# Sch_ma_Global.net
KiCad netlist of a schematic drawn in Altium Designer
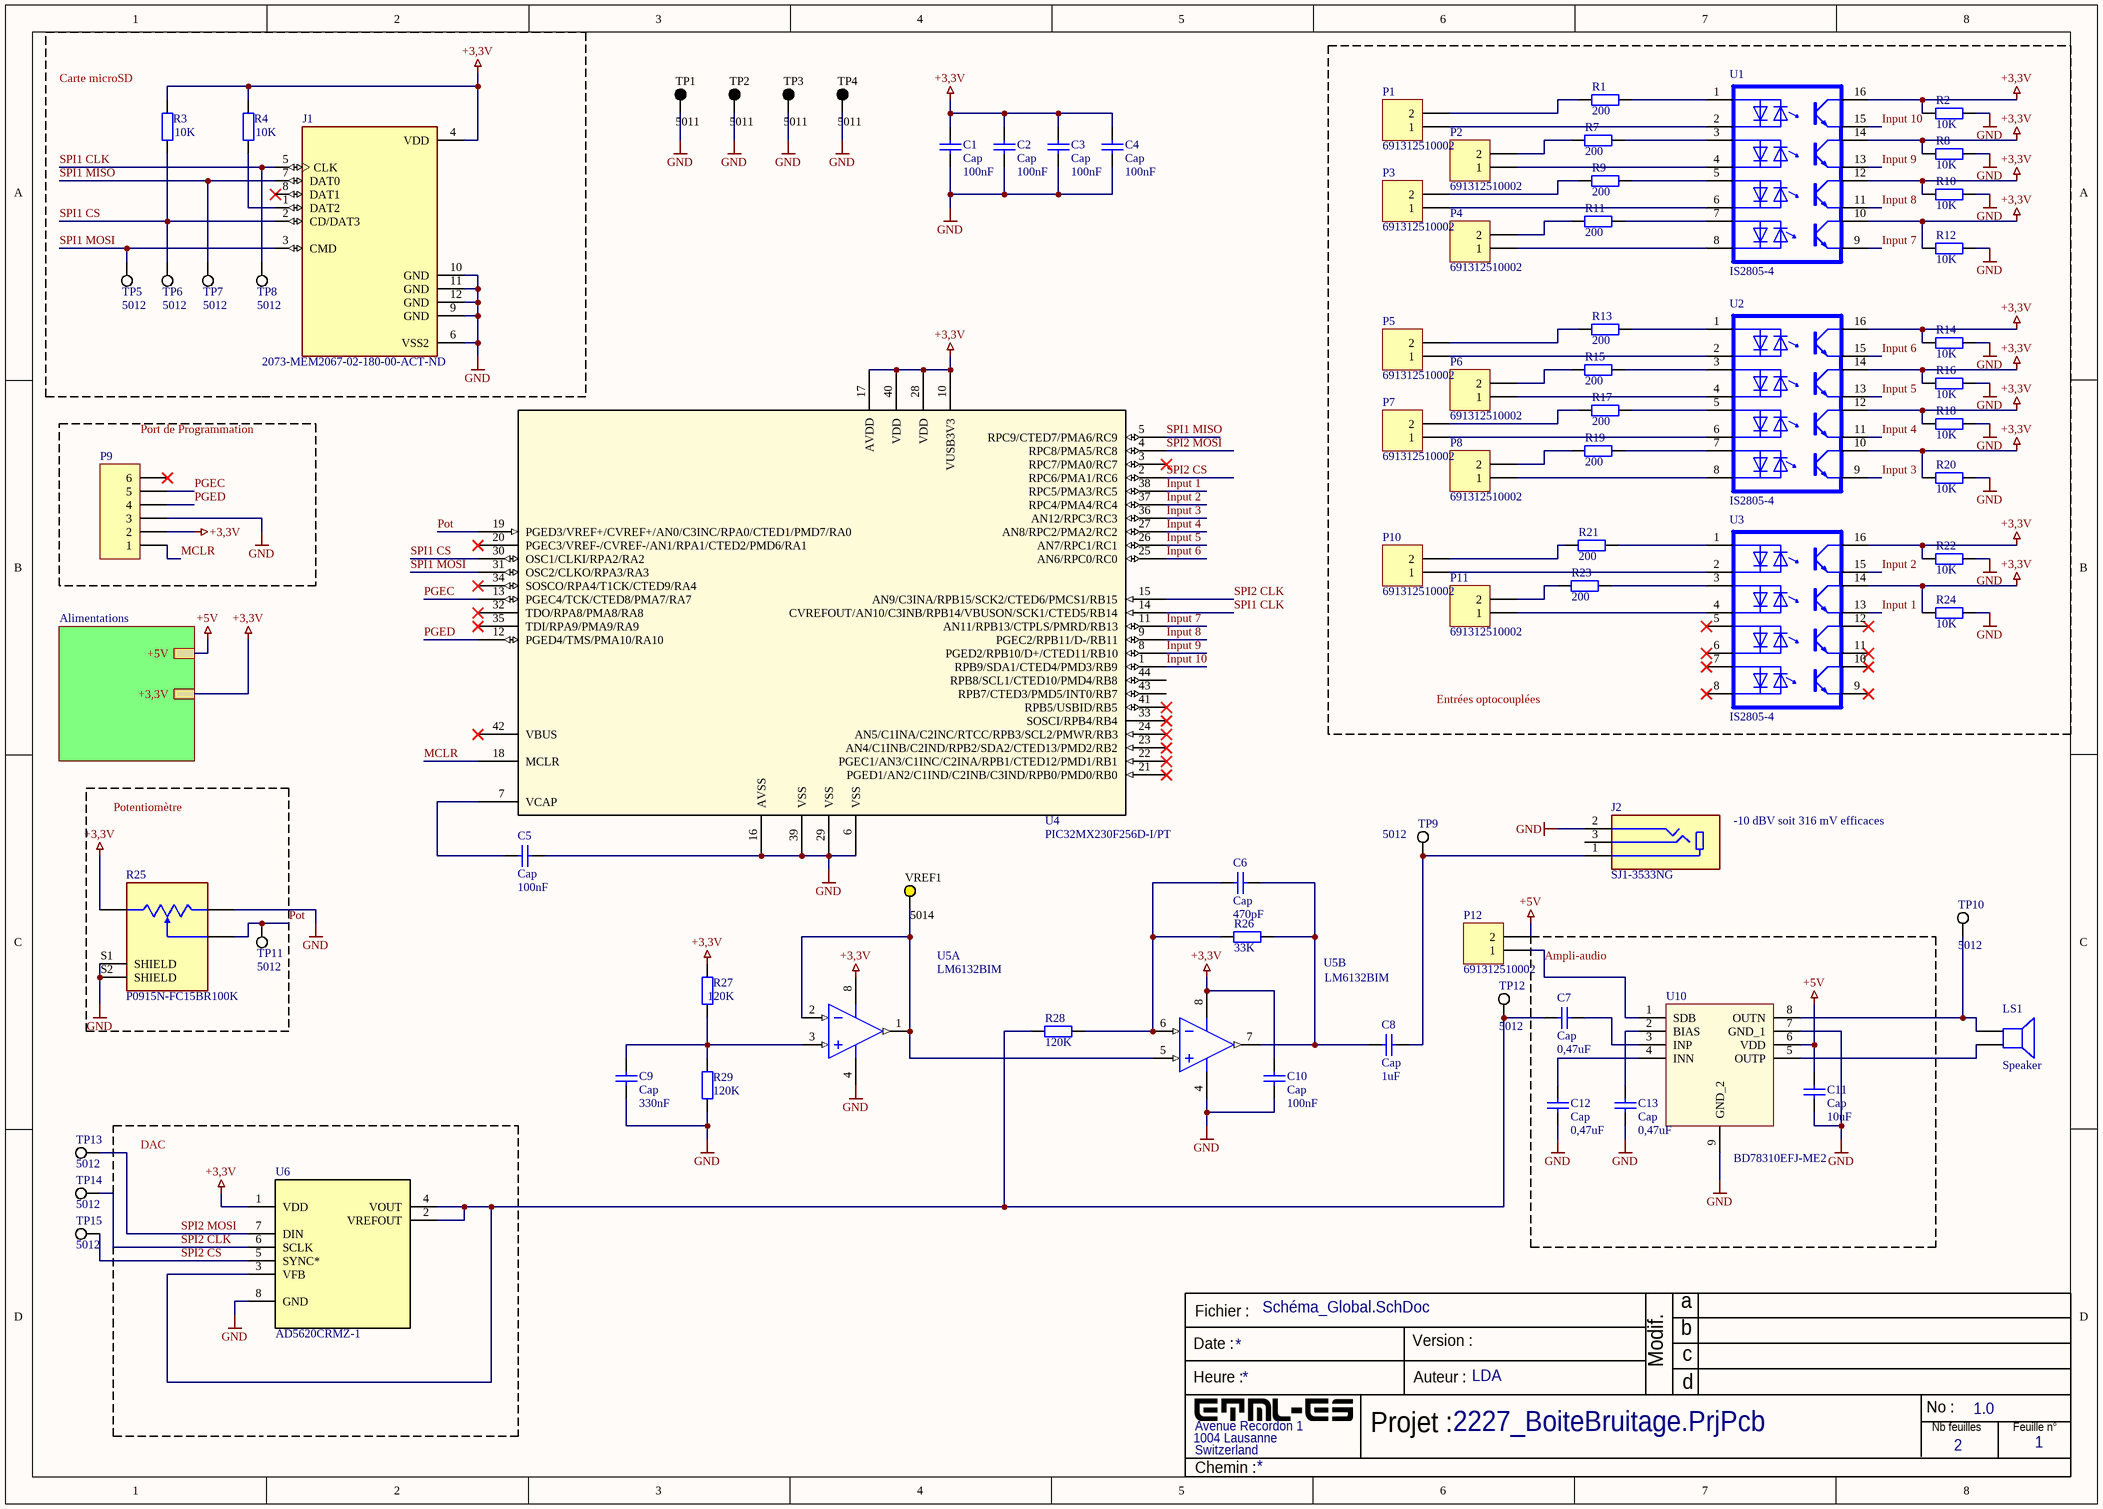
[diagram p0: Schéma_Global.SchDoc]

(export (version "E")
  (design (tool "Eeschema 10.0.6"))
  (components
    (comp (ref "C1")
      (value "Cap")
      (footprint "C0805")
      (description "Capacitor")
      (fields (field (name "ALTIUM_VALUE") "100nF") (field (name "PUBLISHER") "Altium Limited"))
      (libsource (lib "Miscellaneous Devices") (part "Cap"))
    )
    (comp (ref "C2")
      (value "Cap")
      (footprint "C0805")
      (description "Capacitor")
      (fields (field (name "ALTIUM_VALUE") "100nF") (field (name "PUBLISHER") "Altium Limited"))
      (libsource (lib "Miscellaneous Devices") (part "Cap"))
    )
    (comp (ref "C3")
      (value "Cap")
      (footprint "C0805")
      (description "Capacitor")
      (fields (field (name "ALTIUM_VALUE") "100nF") (field (name "PUBLISHER") "Altium Limited"))
      (libsource (lib "Miscellaneous Devices") (part "Cap"))
    )
    (comp (ref "C4")
      (value "Cap")
      (footprint "C0805")
      (description "Capacitor")
      (fields (field (name "ALTIUM_VALUE") "100nF") (field (name "PUBLISHER") "Altium Limited"))
      (libsource (lib "Miscellaneous Devices") (part "Cap"))
    )
    (comp (ref "C5")
      (value "Cap")
      (footprint "C0805")
      (description "Capacitor")
      (fields (field (name "ALTIUM_VALUE") "100nF") (field (name "PUBLISHER") "Altium Limited"))
      (libsource (lib "Miscellaneous Devices") (part "Cap"))
    )
    (comp (ref "C6")
      (value "Cap")
      (footprint "C0805")
      (description "Capacitor")
      (fields (field (name "ALTIUM_VALUE") "470pF") (field (name "PUBLISHER") "Altium Limited"))
      (libsource (lib "Miscellaneous Devices") (part "Cap"))
    )
    (comp (ref "C7")
      (value "Cap")
      (footprint "C0805")
      (description "Capacitor")
      (fields (field (name "ALTIUM_VALUE") "0,47uF") (field (name "PUBLISHER") "Altium Limited"))
      (libsource (lib "Miscellaneous Devices") (part "Cap"))
    )
    (comp (ref "C8")
      (value "Cap")
      (footprint "C0805")
      (description "Capacitor")
      (fields (field (name "ALTIUM_VALUE") "1uF") (field (name "PUBLISHER") "Altium Limited"))
      (libsource (lib "Miscellaneous Devices") (part "Cap"))
    )
    (comp (ref "C9")
      (value "Cap")
      (footprint "C0805")
      (description "Capacitor")
      (fields (field (name "ALTIUM_VALUE") "330nF") (field (name "PUBLISHER") "Altium Limited"))
      (libsource (lib "Miscellaneous Devices") (part "Cap"))
    )
    (comp (ref "C10")
      (value "Cap")
      (footprint "C0805")
      (description "Capacitor")
      (fields (field (name "ALTIUM_VALUE") "100nF") (field (name "PUBLISHER") "Altium Limited"))
      (libsource (lib "Miscellaneous Devices") (part "Cap"))
    )
    (comp (ref "C11")
      (value "Cap")
      (footprint "C0805")
      (description "Capacitor")
      (fields (field (name "ALTIUM_VALUE") "10uF") (field (name "PUBLISHER") "Altium Limited"))
      (libsource (lib "Miscellaneous Devices") (part "Cap"))
    )
    (comp (ref "C12")
      (value "Cap")
      (footprint "C0805")
      (description "Capacitor")
      (fields (field (name "ALTIUM_VALUE") "0,47uF") (field (name "PUBLISHER") "Altium Limited"))
      (libsource (lib "Miscellaneous Devices") (part "Cap"))
    )
    (comp (ref "C13")
      (value "Cap")
      (footprint "C0805")
      (description "Capacitor")
      (fields (field (name "ALTIUM_VALUE") "0,47uF") (field (name "PUBLISHER") "Altium Limited"))
      (libsource (lib "Miscellaneous Devices") (part "Cap"))
    )
    (comp (ref "J1")
      (value "2073-MEM2067-02-180-00-ACT-ND")
      (footprint "GCT_MEM2067-02-180-00-A_REVB")
      (description "2 In 1 Connector Sd+mmc")
      (fields (field (name "MP") "GMC020080HR") (field (name "MF") "Amphenol ICC (Commercial Products)"))
      (libsource (lib "2227_BoiteBruitage") (part "GMC020080HR"))
    )
    (comp (ref "J2")
      (value "SJ1-3533NG")
      (footprint "CUI_SJ1-3533NG")
      (description "3.5 mm Right-Angle Stereo Jack, 3 Pin PCB Mount, Isolated Ground")
      (fields (field (name "MF") "{'manufacturer': u'CUI'}"))
      (libsource (lib "2227_BoiteBruitage") (part "SJ1-3533NG"))
    )
    (comp (ref "LS1")
      (value "Speaker")
      (footprint "PIN2")
      (description "Loudspeaker")
      (fields (field (name "PUBLISHER") "Altium Limited"))
      (libsource (lib "Miscellaneous Devices") (part "Speaker"))
    )
    (comp (ref "P1")
      (value "691312510002")
      (footprint "691312710002")
      (description "Header, 2-Pin")
      (fields (field (name "PUBLISHER") "Altium Limited"))
      (libsource (lib "Miscellaneous Connectors") (part "MHDR1X2"))
    )
    (comp (ref "P2")
      (value "691312510002")
      (footprint "691312710002")
      (description "Header, 2-Pin")
      (fields (field (name "PUBLISHER") "Altium Limited"))
      (libsource (lib "Miscellaneous Connectors") (part "MHDR1X2"))
    )
    (comp (ref "P3")
      (value "691312510002")
      (footprint "691312710002")
      (description "Header, 2-Pin")
      (fields (field (name "PUBLISHER") "Altium Limited"))
      (libsource (lib "Miscellaneous Connectors") (part "MHDR1X2"))
    )
    (comp (ref "P4")
      (value "691312510002")
      (footprint "691312710002")
      (description "Header, 2-Pin")
      (fields (field (name "PUBLISHER") "Altium Limited"))
      (libsource (lib "Miscellaneous Connectors") (part "MHDR1X2"))
    )
    (comp (ref "P5")
      (value "691312510002")
      (footprint "691312710002")
      (description "Header, 2-Pin")
      (fields (field (name "PUBLISHER") "Altium Limited"))
      (libsource (lib "Miscellaneous Connectors") (part "MHDR1X2"))
    )
    (comp (ref "P6")
      (value "691312510002")
      (footprint "691312710002")
      (description "Header, 2-Pin")
      (fields (field (name "PUBLISHER") "Altium Limited"))
      (libsource (lib "Miscellaneous Connectors") (part "MHDR1X2"))
    )
    (comp (ref "P7")
      (value "691312510002")
      (footprint "691312710002")
      (description "Header, 2-Pin")
      (fields (field (name "PUBLISHER") "Altium Limited"))
      (libsource (lib "Miscellaneous Connectors") (part "MHDR1X2"))
    )
    (comp (ref "P8")
      (value "691312510002")
      (footprint "691312710002")
      (description "Header, 2-Pin")
      (fields (field (name "PUBLISHER") "Altium Limited"))
      (libsource (lib "Miscellaneous Connectors") (part "MHDR1X2"))
    )
    (comp (ref "P9")
      (value "76384-406LF")
      (footprint "HDR1X6")
      (description "Header, 6-Pin")
      (fields (field (name "PUBLISHER") "Altium Limited"))
      (libsource (lib "Miscellaneous Connectors") (part "Header 6"))
    )
    (comp (ref "P10")
      (value "691312510002")
      (footprint "691312710002")
      (description "Header, 2-Pin")
      (fields (field (name "PUBLISHER") "Altium Limited"))
      (libsource (lib "Miscellaneous Connectors") (part "MHDR1X2"))
    )
    (comp (ref "P11")
      (value "691312510002")
      (footprint "691312710002")
      (description "Header, 2-Pin")
      (fields (field (name "PUBLISHER") "Altium Limited"))
      (libsource (lib "Miscellaneous Connectors") (part "MHDR1X2"))
    )
    (comp (ref "P12")
      (value "691312510002")
      (footprint "MHDR1X2")
      (description "Header, 2-Pin")
      (fields (field (name "PUBLISHER") "Altium Limited"))
      (libsource (lib "Miscellaneous Connectors") (part "MHDR1X2"))
    )
    (comp (ref "R1")
      (value "200")
      (footprint "C1206")
      (description "Resistor")
      (fields (field (name "Comment") "Res2") (field (name "PUBLISHER") "Altium Limited"))
      (libsource (lib "Miscellaneous Devices") (part "Res2"))
    )
    (comp (ref "R2")
      (value "10K")
      (footprint "C1206")
      (description "Resistor")
      (fields (field (name "Comment") "Res2") (field (name "PUBLISHER") "Altium Limited"))
      (libsource (lib "Miscellaneous Devices") (part "Res2"))
    )
    (comp (ref "R3")
      (value "10K")
      (footprint "C1206")
      (description "Resistor")
      (fields (field (name "Comment") "Res2") (field (name "PUBLISHER") "Altium Limited"))
      (libsource (lib "") (part "Res2_1"))
    )
    (comp (ref "R4")
      (value "10K")
      (footprint "C1206")
      (description "Resistor")
      (fields (field (name "Comment") "Res2") (field (name "PUBLISHER") "Altium Limited"))
      (libsource (lib "") (part "Res2_1"))
    )
    (comp (ref "R7")
      (value "200")
      (footprint "C1206")
      (description "Resistor")
      (fields (field (name "Comment") "Res2") (field (name "PUBLISHER") "Altium Limited"))
      (libsource (lib "Miscellaneous Devices") (part "Res2"))
    )
    (comp (ref "R8")
      (value "10K")
      (footprint "C1206")
      (description "Resistor")
      (fields (field (name "Comment") "Res2") (field (name "PUBLISHER") "Altium Limited"))
      (libsource (lib "Miscellaneous Devices") (part "Res2"))
    )
    (comp (ref "R9")
      (value "200")
      (footprint "C1206")
      (description "Resistor")
      (fields (field (name "Comment") "Res2") (field (name "PUBLISHER") "Altium Limited"))
      (libsource (lib "Miscellaneous Devices") (part "Res2"))
    )
    (comp (ref "R10")
      (value "10K")
      (footprint "C1206")
      (description "Resistor")
      (fields (field (name "Comment") "Res2") (field (name "PUBLISHER") "Altium Limited"))
      (libsource (lib "Miscellaneous Devices") (part "Res2"))
    )
    (comp (ref "R11")
      (value "200")
      (footprint "C1206")
      (description "Resistor")
      (fields (field (name "Comment") "Res2") (field (name "PUBLISHER") "Altium Limited"))
      (libsource (lib "Miscellaneous Devices") (part "Res2"))
    )
    (comp (ref "R12")
      (value "10K")
      (footprint "C1206")
      (description "Resistor")
      (fields (field (name "Comment") "Res2") (field (name "PUBLISHER") "Altium Limited"))
      (libsource (lib "Miscellaneous Devices") (part "Res2"))
    )
    (comp (ref "R13")
      (value "200")
      (footprint "C1206")
      (description "Resistor")
      (fields (field (name "Comment") "Res2") (field (name "PUBLISHER") "Altium Limited"))
      (libsource (lib "Miscellaneous Devices") (part "Res2"))
    )
    (comp (ref "R14")
      (value "10K")
      (footprint "C1206")
      (description "Resistor")
      (fields (field (name "Comment") "Res2") (field (name "PUBLISHER") "Altium Limited"))
      (libsource (lib "Miscellaneous Devices") (part "Res2"))
    )
    (comp (ref "R15")
      (value "200")
      (footprint "C1206")
      (description "Resistor")
      (fields (field (name "Comment") "Res2") (field (name "PUBLISHER") "Altium Limited"))
      (libsource (lib "Miscellaneous Devices") (part "Res2"))
    )
    (comp (ref "R16")
      (value "10K")
      (footprint "C1206")
      (description "Resistor")
      (fields (field (name "Comment") "Res2") (field (name "PUBLISHER") "Altium Limited"))
      (libsource (lib "Miscellaneous Devices") (part "Res2"))
    )
    (comp (ref "R17")
      (value "200")
      (footprint "C1206")
      (description "Resistor")
      (fields (field (name "Comment") "Res2") (field (name "PUBLISHER") "Altium Limited"))
      (libsource (lib "Miscellaneous Devices") (part "Res2"))
    )
    (comp (ref "R18")
      (value "10K")
      (footprint "C1206")
      (description "Resistor")
      (fields (field (name "Comment") "Res2") (field (name "PUBLISHER") "Altium Limited"))
      (libsource (lib "Miscellaneous Devices") (part "Res2"))
    )
    (comp (ref "R19")
      (value "200")
      (footprint "C1206")
      (description "Resistor")
      (fields (field (name "Comment") "Res2") (field (name "PUBLISHER") "Altium Limited"))
      (libsource (lib "Miscellaneous Devices") (part "Res2"))
    )
    (comp (ref "R20")
      (value "10K")
      (footprint "C1206")
      (description "Resistor")
      (fields (field (name "Comment") "Res2") (field (name "PUBLISHER") "Altium Limited"))
      (libsource (lib "Miscellaneous Devices") (part "Res2"))
    )
    (comp (ref "R21")
      (value "200")
      (footprint "C1206")
      (description "Resistor")
      (fields (field (name "Comment") "Res2") (field (name "PUBLISHER") "Altium Limited"))
      (libsource (lib "Miscellaneous Devices") (part "Res2"))
    )
    (comp (ref "R22")
      (value "10K")
      (footprint "C1206")
      (description "Resistor")
      (fields (field (name "Comment") "Res2") (field (name "PUBLISHER") "Altium Limited"))
      (libsource (lib "Miscellaneous Devices") (part "Res2"))
    )
    (comp (ref "R23")
      (value "200")
      (footprint "C1206")
      (description "Resistor")
      (fields (field (name "Comment") "Res2") (field (name "PUBLISHER") "Altium Limited"))
      (libsource (lib "Miscellaneous Devices") (part "Res2"))
    )
    (comp (ref "R24")
      (value "10K")
      (footprint "C1206")
      (description "Resistor")
      (fields (field (name "Comment") "Res2") (field (name "PUBLISHER") "Altium Limited"))
      (libsource (lib "Miscellaneous Devices") (part "Res2"))
    )
    (comp (ref "R25")
      (value "P0915N-FC15BR100K")
      (footprint "TRIM_P0915N-FC15BR100K")
      (fields (field (name "MF") "BI Technologies (TT electronics)"))
      (libsource (lib "2227_BoiteBruitage") (part "P0915N-FC15BR100K"))
    )
    (comp (ref "R26")
      (value "33K")
      (footprint "C1206")
      (description "Resistor")
      (fields (field (name "Comment") "Res2") (field (name "PUBLISHER") "Altium Limited"))
      (libsource (lib "Miscellaneous Devices") (part "Res2"))
    )
    (comp (ref "R27")
      (value "120K")
      (footprint "C1206")
      (description "Resistor")
      (fields (field (name "Comment") "Res2") (field (name "PUBLISHER") "Altium Limited"))
      (libsource (lib "") (part "Res2_1"))
    )
    (comp (ref "R28")
      (value "120K")
      (footprint "C1206")
      (description "Resistor")
      (fields (field (name "Comment") "Res2") (field (name "PUBLISHER") "Altium Limited"))
      (libsource (lib "Miscellaneous Devices") (part "Res2"))
    )
    (comp (ref "R29")
      (value "120K")
      (footprint "C1206")
      (description "Resistor")
      (fields (field (name "Comment") "Res2") (field (name "PUBLISHER") "Altium Limited"))
      (libsource (lib "") (part "Res2_1"))
    )
    (comp (ref "TP1")
      (value "5011")
      (footprint "KSTN-5011_V")
      (description "Test Point, Black, Through Hole, RoHS, Bulk")
      (fields (field (name "MANUFACTURER") "Keystone"))
      (libsource (lib "Altium Content Vault") (part "TESTPOINT_BLACK"))
    )
    (comp (ref "TP2")
      (value "5011")
      (footprint "KSTN-5011_V")
      (description "Test Point, Black, Through Hole, RoHS, Bulk")
      (fields (field (name "MANUFACTURER") "Keystone"))
      (libsource (lib "Altium Content Vault") (part "TESTPOINT_BLACK"))
    )
    (comp (ref "TP3")
      (value "5011")
      (footprint "KSTN-5011_V")
      (description "Test Point, Black, Through Hole, RoHS, Bulk")
      (fields (field (name "MANUFACTURER") "Keystone"))
      (libsource (lib "Altium Content Vault") (part "TESTPOINT_BLACK"))
    )
    (comp (ref "TP4")
      (value "5011")
      (footprint "KSTN-5011_V")
      (description "Test Point, Black, Through Hole, RoHS, Bulk")
      (fields (field (name "MANUFACTURER") "Keystone"))
      (libsource (lib "Altium Content Vault") (part "TESTPOINT_BLACK"))
    )
    (comp (ref "TP5")
      (value "5012")
      (footprint "KSTN-5012_V")
      (description "Test Point, White, Through Hole, RoHS, Bulk")
      (fields (field (name "MANUFACTURER") "Keystone"))
      (libsource (lib "Altium Content Vault") (part "TESTPOINT_WHITE"))
    )
    (comp (ref "TP6")
      (value "5012")
      (footprint "KSTN-5012_V")
      (description "Test Point, White, Through Hole, RoHS, Bulk")
      (fields (field (name "MANUFACTURER") "Keystone"))
      (libsource (lib "Altium Content Vault") (part "TESTPOINT_WHITE"))
    )
    (comp (ref "TP7")
      (value "5012")
      (footprint "KSTN-5012_V")
      (description "Test Point, White, Through Hole, RoHS, Bulk")
      (fields (field (name "MANUFACTURER") "Keystone"))
      (libsource (lib "Altium Content Vault") (part "TESTPOINT_WHITE"))
    )
    (comp (ref "TP8")
      (value "5012")
      (footprint "KSTN-5012_V")
      (description "Test Point, White, Through Hole, RoHS, Bulk")
      (fields (field (name "MANUFACTURER") "Keystone"))
      (libsource (lib "Altium Content Vault") (part "TESTPOINT_WHITE"))
    )
    (comp (ref "TP9")
      (value "5012")
      (footprint "KSTN-5012_V")
      (description "Test Point, White, Through Hole, RoHS, Bulk")
      (fields (field (name "MANUFACTURER") "Keystone"))
      (libsource (lib "Altium Content Vault") (part "TESTPOINT_WHITE"))
    )
    (comp (ref "TP10")
      (value "5012")
      (footprint "KSTN-5012_V")
      (description "Test Point, White, Through Hole, RoHS, Bulk")
      (fields (field (name "MANUFACTURER") "Keystone"))
      (libsource (lib "Altium Content Vault") (part "TESTPOINT_WHITE"))
    )
    (comp (ref "TP11")
      (value "5012")
      (footprint "KSTN-5012_V")
      (description "Test Point, White, Through Hole, RoHS, Bulk")
      (fields (field (name "MANUFACTURER") "Keystone"))
      (libsource (lib "Altium Content Vault") (part "TESTPOINT_WHITE"))
    )
    (comp (ref "TP12")
      (value "5012")
      (footprint "KSTN-5012_V")
      (description "Test Point, White, Through Hole, RoHS, Bulk")
      (fields (field (name "MANUFACTURER") "Keystone"))
      (libsource (lib "Altium Content Vault") (part "TESTPOINT_WHITE"))
    )
    (comp (ref "TP13")
      (value "5012")
      (footprint "KSTN-5012_V")
      (description "Test Point, White, Through Hole, RoHS, Bulk")
      (fields (field (name "MANUFACTURER") "Keystone"))
      (libsource (lib "Altium Content Vault") (part "TESTPOINT_WHITE"))
    )
    (comp (ref "TP14")
      (value "5012")
      (footprint "KSTN-5012_V")
      (description "Test Point, White, Through Hole, RoHS, Bulk")
      (fields (field (name "MANUFACTURER") "Keystone"))
      (libsource (lib "Altium Content Vault") (part "TESTPOINT_WHITE"))
    )
    (comp (ref "TP15")
      (value "5012")
      (footprint "KSTN-5012_V")
      (description "Test Point, White, Through Hole, RoHS, Bulk")
      (fields (field (name "MANUFACTURER") "Keystone"))
      (libsource (lib "Altium Content Vault") (part "TESTPOINT_WHITE"))
    )
    (comp (ref "U1")
      (value "IS2805-4")
      (footprint "Opto_SOIC")
      (fields (field (name "MP") "VOS615A-1X001T"))
      (libsource (lib "2227_BoiteBruitage") (part "IS2805-4"))
    )
    (comp (ref "U2")
      (value "IS2805-4")
      (footprint "Opto_SOIC")
      (fields (field (name "MP") "VOS615A-1X001T"))
      (libsource (lib "2227_BoiteBruitage") (part "IS2805-4"))
    )
    (comp (ref "U3")
      (value "IS2805-4")
      (footprint "Opto_SOIC")
      (fields (field (name "MP") "VOS615A-1X001T"))
      (libsource (lib "2227_BoiteBruitage") (part "IS2805-4"))
    )
    (comp (ref "U4")
      (value "PIC32MX230F256D-I/PT")
      (footprint "TQFP44_PT_MCH")
      (description "No Description Available")
      (fields (field (name "COPYRIGHT") "Copyright (C) 2023 Ultra Librarian. All rights reserved."))
      (libsource (lib "2227_BoiteBruitage") (part "PIC32MX230F256D-I/PT"))
    )
    (comp (ref "U5")
      (value "LM6132BIM")
      (footprint "D0008A_N")
      (description "Dual Low Power 10 MHz Rail-to-Rail I/O Operational Amplifier, 8-pin Narrow SOIC")
      (fields (field (name "MANUFACTURER") "Texas Instruments"))
      (libsource (lib "Altium Content Vault") (part "AMP-OPA-LM6132-8"))
    )
    (comp (ref "U6")
      (value "AD5620CRMZ-1")
      (footprint "SOP65P490X110-8N")
      (description "Single, 12-Bit nanoDACÂ® with 5 ppm/Â°C On-Chip Reference in SOT-23")
      (fields (field (name "MF") "Analog Devices"))
      (libsource (lib "2227_BoiteBruitage") (part "AD5620CRMZ-1"))
    )
    (comp (ref "U10")
      (value "BD78310EFJ-ME2")
      (footprint "AOP_HASOP-J8")
      (description "1.2W MONAURAL SPEAKER AMPLIFIER")
      (fields (field (name "MOUSER PART NUMBER") "755-BD78310EFJ-ME2"))
      (libsource (lib "2227_BoiteBruitage") (part "BD78310EFJ-ME2"))
    )
    (comp (ref "VREF1")
      (value "5014")
      (footprint "KSTN-5014_V")
      (description "Test Point, Yellow, Through Hole, RoHS, Bulk")
      (fields (field (name "MANUFACTURER") "Keystone"))
      (libsource (lib "Altium Content Vault") (part "TESTPOINT_YELLOW"))
    )
  )
  (nets
    (net (code "1") (name "+3,3V") (class "Default")
      (node (ref "C1") (pin "1") (pinfunction "1_1") (pintype "passive"))
      (node (ref "C10") (pin "2") (pinfunction "2_2") (pintype "passive"))
      (node (ref "C2") (pin "1") (pinfunction "1_1") (pintype "passive"))
      (node (ref "C3") (pin "1") (pinfunction "1_1") (pintype "passive"))
      (node (ref "C4") (pin "1") (pinfunction "1_1") (pintype "passive"))
      (node (ref "J1") (pin "4") (pinfunction "VDD_4") (pintype "power_in"))
      (node (ref "P9") (pin "2") (pinfunction "2_2") (pintype "passive"))
      (node (ref "R10") (pin "1") (pinfunction "1_1") (pintype "passive"))
      (node (ref "R12") (pin "1") (pinfunction "1_1") (pintype "passive"))
      (node (ref "R14") (pin "1") (pinfunction "1_1") (pintype "passive"))
      (node (ref "R16") (pin "1") (pinfunction "1_1") (pintype "passive"))
      (node (ref "R18") (pin "1") (pinfunction "1_1") (pintype "passive"))
      (node (ref "R2") (pin "1") (pinfunction "1_1") (pintype "passive"))
      (node (ref "R20") (pin "1") (pinfunction "1_1") (pintype "passive"))
      (node (ref "R22") (pin "1") (pinfunction "1_1") (pintype "passive"))
      (node (ref "R24") (pin "1") (pinfunction "1_1") (pintype "passive"))
      (node (ref "R25") (pin "1") (pinfunction "1_1") (pintype "passive"))
      (node (ref "R27") (pin "2") (pinfunction "2_2") (pintype "passive"))
      (node (ref "R3") (pin "2") (pinfunction "2_2") (pintype "passive"))
      (node (ref "R4") (pin "2") (pinfunction "2_2") (pintype "passive"))
      (node (ref "R8") (pin "1") (pinfunction "1_1") (pintype "passive"))
      (node (ref "U1") (pin "10") (pinfunction "CO_10") (pintype "passive"))
      (node (ref "U1") (pin "12") (pinfunction "CO_12") (pintype "passive"))
      (node (ref "U1") (pin "14") (pinfunction "CO_14") (pintype "passive"))
      (node (ref "U1") (pin "16") (pinfunction "CO_16") (pintype "passive"))
      (node (ref "U2") (pin "10") (pinfunction "CO_10") (pintype "passive"))
      (node (ref "U2") (pin "12") (pinfunction "CO_12") (pintype "passive"))
      (node (ref "U2") (pin "14") (pinfunction "CO_14") (pintype "passive"))
      (node (ref "U2") (pin "16") (pinfunction "CO_16") (pintype "passive"))
      (node (ref "U3") (pin "14") (pinfunction "CO_14") (pintype "passive"))
      (node (ref "U3") (pin "16") (pinfunction "CO_16") (pintype "passive"))
      (node (ref "U4") (pin "10") (pinfunction "VUSB3V3_10") (pintype "power_in"))
      (node (ref "U4") (pin "17") (pinfunction "AVDD_17") (pintype "power_in"))
      (node (ref "U4") (pin "28") (pinfunction "VDD_28") (pintype "power_in"))
      (node (ref "U4") (pin "40") (pinfunction "VDD_40") (pintype "power_in"))
      (node (ref "U5") (pin "8") (pinfunction "V+_8") (pintype "power_in"))
      (node (ref "U6") (pin "1") (pinfunction "VDD_1") (pintype "power_in"))
    )
    (net (code "2") (name "+5V") (class "Default")
      (node (ref "C11") (pin "1") (pinfunction "1_1") (pintype "passive"))
      (node (ref "P12") (pin "2") (pinfunction "2_2") (pintype "passive"))
      (node (ref "U10") (pin "6") (pinfunction "VDD_6") (pintype "passive"))
    )
    (net (code "3") (name "/Input 1") (class "Default")
      (node (ref "U3") (pin "13") (pinfunction "E_13") (pintype "passive"))
      (node (ref "U4") (pin "38") (pinfunction "RPC5/PMA3/RC5_38") (pintype "bidirectional"))
    )
    (net (code "4") (name "/Input 2") (class "Default")
      (node (ref "U3") (pin "15") (pinfunction "E_15") (pintype "passive"))
      (node (ref "U4") (pin "37") (pinfunction "RPC4/PMA4/RC4_37") (pintype "bidirectional"))
    )
    (net (code "5") (name "/Input 3") (class "Default")
      (node (ref "U2") (pin "9") (pinfunction "E_9") (pintype "passive"))
      (node (ref "U4") (pin "36") (pinfunction "AN12/RPC3/RC3_36") (pintype "bidirectional"))
    )
    (net (code "6") (name "/Input 4") (class "Default")
      (node (ref "U2") (pin "11") (pinfunction "E_11") (pintype "passive"))
      (node (ref "U4") (pin "27") (pinfunction "AN8/RPC2/PMA2/RC2_27") (pintype "bidirectional"))
    )
    (net (code "7") (name "/Input 5") (class "Default")
      (node (ref "U2") (pin "13") (pinfunction "E_13") (pintype "passive"))
      (node (ref "U4") (pin "26") (pinfunction "AN7/RPC1/RC1_26") (pintype "bidirectional"))
    )
    (net (code "8") (name "/Input 6") (class "Default")
      (node (ref "U2") (pin "15") (pinfunction "E_15") (pintype "passive"))
      (node (ref "U4") (pin "25") (pinfunction "AN6/RPC0/RC0_25") (pintype "bidirectional"))
    )
    (net (code "9") (name "/Input 7") (class "Default")
      (node (ref "U1") (pin "9") (pinfunction "E_9") (pintype "passive"))
      (node (ref "U4") (pin "11") (pinfunction "AN11/RPB13/CTPLS/PMRD/RB13_11") (pintype "bidirectional"))
    )
    (net (code "10") (name "/Input 8") (class "Default")
      (node (ref "U1") (pin "11") (pinfunction "E_11") (pintype "passive"))
      (node (ref "U4") (pin "9") (pinfunction "PGEC2/RPB11/D-/RB11_9") (pintype "bidirectional"))
    )
    (net (code "11") (name "/Input 9") (class "Default")
      (node (ref "U1") (pin "13") (pinfunction "E_13") (pintype "passive"))
      (node (ref "U4") (pin "8") (pinfunction "PGED2/RPB10/D+/CTED11/RB10_8") (pintype "bidirectional"))
    )
    (net (code "12") (name "/Input 10") (class "Default")
      (node (ref "U1") (pin "15") (pinfunction "E_15") (pintype "passive"))
      (node (ref "U4") (pin "1") (pinfunction "RPB9/SDA1/CTED4/PMD3/RB9_1") (pintype "bidirectional"))
    )
    (net (code "13") (name "/MCLR") (class "Default")
      (node (ref "P9") (pin "1") (pinfunction "1_1") (pintype "passive"))
      (node (ref "U4") (pin "18") (pinfunction "MCLR_18") (pintype "passive"))
    )
    (net (code "14") (name "/PGEC") (class "Default")
      (node (ref "P9") (pin "5") (pinfunction "5_5") (pintype "passive"))
      (node (ref "U4") (pin "13") (pinfunction "PGEC4/TCK/CTED8/PMA7/RA7_13") (pintype "bidirectional"))
    )
    (net (code "15") (name "/PGED") (class "Default")
      (node (ref "P9") (pin "4") (pinfunction "4_4") (pintype "passive"))
      (node (ref "U4") (pin "12") (pinfunction "PGED4/TMS/PMA10/RA10_12") (pintype "bidirectional"))
    )
    (net (code "16") (name "/Pot") (class "Default")
      (node (ref "R25") (pin "2") (pinfunction "2_2") (pintype "passive"))
      (node (ref "TP11") (pin "1") (pinfunction "1_1") (pintype "passive"))
      (node (ref "U4") (pin "19") (pinfunction "PGED3/VREF+/CVREF+/AN0/C3INC/RPA0/CTED1/PMD7/RA0_19") (pintype "input"))
    )
    (net (code "17") (name "/SPI1 CLK") (class "Default")
      (node (ref "J1") (pin "5") (pinfunction "CLK_5") (pintype "bidirectional"))
      (node (ref "TP8") (pin "1") (pinfunction "1_1") (pintype "passive"))
      (node (ref "U4") (pin "14") (pinfunction "CVREFOUT/AN10/C3INB/RPB14/VBUSON/SCK1/CTED5/RB14_14") (pintype "input"))
    )
    (net (code "18") (name "/SPI1 CS") (class "Default")
      (node (ref "J1") (pin "2") (pinfunction "CD/DAT3_2") (pintype "bidirectional"))
      (node (ref "R3") (pin "1") (pinfunction "1_1") (pintype "passive"))
      (node (ref "TP6") (pin "1") (pinfunction "1_1") (pintype "passive"))
      (node (ref "U4") (pin "30") (pinfunction "OSC1/CLKI/RPA2/RA2_30") (pintype "bidirectional"))
    )
    (net (code "19") (name "/SPI1 MISO") (class "Default")
      (node (ref "J1") (pin "7") (pinfunction "DAT0_7") (pintype "bidirectional"))
      (node (ref "TP7") (pin "1") (pinfunction "1_1") (pintype "passive"))
      (node (ref "U4") (pin "5") (pinfunction "RPC9/CTED7/PMA6/RC9_5") (pintype "bidirectional"))
    )
    (net (code "20") (name "/SPI1 MOSI") (class "Default")
      (node (ref "J1") (pin "3") (pinfunction "CMD_3") (pintype "bidirectional"))
      (node (ref "TP5") (pin "1") (pinfunction "1_1") (pintype "passive"))
      (node (ref "U4") (pin "31") (pinfunction "OSC2/CLKO/RPA3/RA3_31") (pintype "bidirectional"))
    )
    (net (code "21") (name "/SPI2 CLK") (class "Default")
      (node (ref "TP14") (pin "1") (pinfunction "1_1") (pintype "passive"))
      (node (ref "U4") (pin "15") (pinfunction "AN9/C3INA/RPB15/SCK2/CTED6/PMCS1/RB15_15") (pintype "input"))
      (node (ref "U6") (pin "6") (pinfunction "SCLK_6") (pintype "passive"))
    )
    (net (code "22") (name "/SPI2 CS") (class "Default")
      (node (ref "TP15") (pin "1") (pinfunction "1_1") (pintype "passive"))
      (node (ref "U4") (pin "2") (pinfunction "RPC6/PMA1/RC6_2") (pintype "bidirectional"))
      (node (ref "U6") (pin "5") (pinfunction "SYNC*_5") (pintype "passive"))
    )
    (net (code "23") (name "/SPI2 MOSI") (class "Default")
      (node (ref "TP13") (pin "1") (pinfunction "1_1") (pintype "passive"))
      (node (ref "U4") (pin "4") (pinfunction "RPC8/PMA5/RC8_4") (pintype "bidirectional"))
      (node (ref "U6") (pin "7") (pinfunction "DIN_7") (pintype "passive"))
    )
    (net (code "24") (name "GND") (class "Default")
      (node (ref "C1") (pin "2") (pinfunction "2_2") (pintype "passive"))
      (node (ref "C10") (pin "1") (pinfunction "1_1") (pintype "passive"))
      (node (ref "C11") (pin "2") (pinfunction "2_2") (pintype "passive"))
      (node (ref "C12") (pin "1") (pinfunction "1_1") (pintype "passive"))
      (node (ref "C13") (pin "1") (pinfunction "1_1") (pintype "passive"))
      (node (ref "C2") (pin "2") (pinfunction "2_2") (pintype "passive"))
      (node (ref "C3") (pin "2") (pinfunction "2_2") (pintype "passive"))
      (node (ref "C4") (pin "2") (pinfunction "2_2") (pintype "passive"))
      (node (ref "C5") (pin "1") (pinfunction "1_1") (pintype "passive"))
      (node (ref "C9") (pin "1") (pinfunction "1_1") (pintype "passive"))
      (node (ref "J1") (pin "10") (pinfunction "GND_10") (pintype "power_in"))
      (node (ref "J1") (pin "11") (pinfunction "GND_11") (pintype "power_in"))
      (node (ref "J1") (pin "12") (pinfunction "GND_12") (pintype "power_in"))
      (node (ref "J1") (pin "6") (pinfunction "VSS2_6") (pintype "power_in"))
      (node (ref "J1") (pin "9") (pinfunction "GND_9") (pintype "power_in"))
      (node (ref "J2") (pin "2") (pinfunction "2_2") (pintype "passive"))
      (node (ref "P9") (pin "3") (pinfunction "3_3") (pintype "passive"))
      (node (ref "R10") (pin "2") (pinfunction "2_2") (pintype "passive"))
      (node (ref "R12") (pin "2") (pinfunction "2_2") (pintype "passive"))
      (node (ref "R14") (pin "2") (pinfunction "2_2") (pintype "passive"))
      (node (ref "R16") (pin "2") (pinfunction "2_2") (pintype "passive"))
      (node (ref "R18") (pin "2") (pinfunction "2_2") (pintype "passive"))
      (node (ref "R2") (pin "2") (pinfunction "2_2") (pintype "passive"))
      (node (ref "R20") (pin "2") (pinfunction "2_2") (pintype "passive"))
      (node (ref "R22") (pin "2") (pinfunction "2_2") (pintype "passive"))
      (node (ref "R24") (pin "2") (pinfunction "2_2") (pintype "passive"))
      (node (ref "R25") (pin "3") (pinfunction "3_3") (pintype "passive"))
      (node (ref "R25") (pin "S1") (pinfunction "SHIELD_S1") (pintype "passive"))
      (node (ref "R25") (pin "S2") (pinfunction "SHIELD_S2") (pintype "passive"))
      (node (ref "R29") (pin "1") (pinfunction "1_1") (pintype "passive"))
      (node (ref "R8") (pin "2") (pinfunction "2_2") (pintype "passive"))
      (node (ref "TP1") (pin "1") (pinfunction "1_1") (pintype "passive"))
      (node (ref "TP2") (pin "1") (pinfunction "1_1") (pintype "passive"))
      (node (ref "TP3") (pin "1") (pinfunction "1_1") (pintype "passive"))
      (node (ref "TP4") (pin "1") (pinfunction "1_1") (pintype "passive"))
      (node (ref "U10") (pin "7") (pinfunction "GND_1_7") (pintype "passive"))
      (node (ref "U10") (pin "9") (pinfunction "GND_2_9") (pintype "passive"))
      (node (ref "U4") (pin "16") (pinfunction "AVSS_16") (pintype "passive"))
      (node (ref "U4") (pin "29") (pinfunction "VSS_29") (pintype "passive"))
      (node (ref "U4") (pin "39") (pinfunction "VSS_39") (pintype "passive"))
      (node (ref "U4") (pin "6") (pinfunction "VSS_6") (pintype "passive"))
      (node (ref "U5") (pin "4") (pinfunction "V-_4") (pintype "power_in"))
      (node (ref "U6") (pin "8") (pinfunction "GND_8") (pintype "passive"))
    )
    (net (code "25") (name "Net-(C8-Pad1)") (class "Default")
      (node (ref "C8") (pin "1") (pinfunction "1_1") (pintype "passive"))
      (node (ref "J2") (pin "1") (pinfunction "1_1") (pintype "passive"))
      (node (ref "TP9") (pin "1") (pinfunction "1_1") (pintype "passive"))
    )
    (net (code "26") (name "Net-(J1-DAT2)") (class "Default")
      (node (ref "J1") (pin "1") (pinfunction "DAT2_1") (pintype "bidirectional"))
      (node (ref "R4") (pin "1") (pinfunction "1_1") (pintype "passive"))
    )
    (net (code "27") (name "Net-(P1-Pad1)") (class "Default")
      (node (ref "P1") (pin "1") (pinfunction "1_1") (pintype "passive"))
      (node (ref "U1") (pin "2") (pinfunction "C_2") (pintype "passive"))
    )
    (net (code "28") (name "Net-(P1-Pad2)") (class "Default")
      (node (ref "P1") (pin "2") (pinfunction "2_2") (pintype "passive"))
      (node (ref "R1") (pin "1") (pinfunction "1_1") (pintype "passive"))
    )
    (net (code "29") (name "Net-(P2-Pad1)") (class "Default")
      (node (ref "P2") (pin "1") (pinfunction "1_1") (pintype "passive"))
      (node (ref "U1") (pin "4") (pinfunction "C_4") (pintype "passive"))
    )
    (net (code "30") (name "Net-(P2-Pad2)") (class "Default")
      (node (ref "P2") (pin "2") (pinfunction "2_2") (pintype "passive"))
      (node (ref "R7") (pin "1") (pinfunction "1_1") (pintype "passive"))
    )
    (net (code "31") (name "Net-(P3-Pad1)") (class "Default")
      (node (ref "P3") (pin "1") (pinfunction "1_1") (pintype "passive"))
      (node (ref "U1") (pin "6") (pinfunction "C_6") (pintype "passive"))
    )
    (net (code "32") (name "Net-(P3-Pad2)") (class "Default")
      (node (ref "P3") (pin "2") (pinfunction "2_2") (pintype "passive"))
      (node (ref "R9") (pin "1") (pinfunction "1_1") (pintype "passive"))
    )
    (net (code "33") (name "Net-(P4-Pad1)") (class "Default")
      (node (ref "P4") (pin "1") (pinfunction "1_1") (pintype "passive"))
      (node (ref "U1") (pin "8") (pinfunction "C_8") (pintype "passive"))
    )
    (net (code "34") (name "Net-(P4-Pad2)") (class "Default")
      (node (ref "P4") (pin "2") (pinfunction "2_2") (pintype "passive"))
      (node (ref "R11") (pin "1") (pinfunction "1_1") (pintype "passive"))
    )
    (net (code "35") (name "Net-(P5-Pad1)") (class "Default")
      (node (ref "P5") (pin "1") (pinfunction "1_1") (pintype "passive"))
      (node (ref "U2") (pin "2") (pinfunction "C_2") (pintype "passive"))
    )
    (net (code "36") (name "Net-(P5-Pad2)") (class "Default")
      (node (ref "P5") (pin "2") (pinfunction "2_2") (pintype "passive"))
      (node (ref "R13") (pin "1") (pinfunction "1_1") (pintype "passive"))
    )
    (net (code "37") (name "Net-(P6-Pad1)") (class "Default")
      (node (ref "P6") (pin "1") (pinfunction "1_1") (pintype "passive"))
      (node (ref "U2") (pin "4") (pinfunction "C_4") (pintype "passive"))
    )
    (net (code "38") (name "Net-(P6-Pad2)") (class "Default")
      (node (ref "P6") (pin "2") (pinfunction "2_2") (pintype "passive"))
      (node (ref "R15") (pin "1") (pinfunction "1_1") (pintype "passive"))
    )
    (net (code "39") (name "Net-(P7-Pad1)") (class "Default")
      (node (ref "P7") (pin "1") (pinfunction "1_1") (pintype "passive"))
      (node (ref "U2") (pin "6") (pinfunction "C_6") (pintype "passive"))
    )
    (net (code "40") (name "Net-(P7-Pad2)") (class "Default")
      (node (ref "P7") (pin "2") (pinfunction "2_2") (pintype "passive"))
      (node (ref "R17") (pin "1") (pinfunction "1_1") (pintype "passive"))
    )
    (net (code "41") (name "Net-(P8-Pad1)") (class "Default")
      (node (ref "P8") (pin "1") (pinfunction "1_1") (pintype "passive"))
      (node (ref "U2") (pin "8") (pinfunction "C_8") (pintype "passive"))
    )
    (net (code "42") (name "Net-(P8-Pad2)") (class "Default")
      (node (ref "P8") (pin "2") (pinfunction "2_2") (pintype "passive"))
      (node (ref "R19") (pin "1") (pinfunction "1_1") (pintype "passive"))
    )
    (net (code "43") (name "Net-(P10-Pad1)") (class "Default")
      (node (ref "P10") (pin "1") (pinfunction "1_1") (pintype "passive"))
      (node (ref "U3") (pin "2") (pinfunction "C_2") (pintype "passive"))
    )
    (net (code "44") (name "Net-(P10-Pad2)") (class "Default")
      (node (ref "P10") (pin "2") (pinfunction "2_2") (pintype "passive"))
      (node (ref "R21") (pin "1") (pinfunction "1_1") (pintype "passive"))
    )
    (net (code "45") (name "Net-(P11-Pad1)") (class "Default")
      (node (ref "P11") (pin "1") (pinfunction "1_1") (pintype "passive"))
      (node (ref "U3") (pin "4") (pinfunction "C_4") (pintype "passive"))
    )
    (net (code "46") (name "Net-(P11-Pad2)") (class "Default")
      (node (ref "P11") (pin "2") (pinfunction "2_2") (pintype "passive"))
      (node (ref "R23") (pin "1") (pinfunction "1_1") (pintype "passive"))
    )
    (net (code "47") (name "Net-(R1-Pad2)") (class "Default")
      (node (ref "R1") (pin "2") (pinfunction "2_2") (pintype "passive"))
      (node (ref "U1") (pin "1") (pinfunction "A_1") (pintype "passive"))
    )
    (net (code "48") (name "Net-(R7-Pad2)") (class "Default")
      (node (ref "R7") (pin "2") (pinfunction "2_2") (pintype "passive"))
      (node (ref "U1") (pin "3") (pinfunction "A_3") (pintype "passive"))
    )
    (net (code "49") (name "Net-(R9-Pad2)") (class "Default")
      (node (ref "R9") (pin "2") (pinfunction "2_2") (pintype "passive"))
      (node (ref "U1") (pin "5") (pinfunction "A_5") (pintype "passive"))
    )
    (net (code "50") (name "Net-(R11-Pad2)") (class "Default")
      (node (ref "R11") (pin "2") (pinfunction "2_2") (pintype "passive"))
      (node (ref "U1") (pin "7") (pinfunction "A_7") (pintype "passive"))
    )
    (net (code "51") (name "Net-(R13-Pad2)") (class "Default")
      (node (ref "R13") (pin "2") (pinfunction "2_2") (pintype "passive"))
      (node (ref "U2") (pin "1") (pinfunction "A_1") (pintype "passive"))
    )
    (net (code "52") (name "Net-(R15-Pad2)") (class "Default")
      (node (ref "R15") (pin "2") (pinfunction "2_2") (pintype "passive"))
      (node (ref "U2") (pin "3") (pinfunction "A_3") (pintype "passive"))
    )
    (net (code "53") (name "Net-(R17-Pad2)") (class "Default")
      (node (ref "R17") (pin "2") (pinfunction "2_2") (pintype "passive"))
      (node (ref "U2") (pin "5") (pinfunction "A_5") (pintype "passive"))
    )
    (net (code "54") (name "Net-(R19-Pad2)") (class "Default")
      (node (ref "R19") (pin "2") (pinfunction "2_2") (pintype "passive"))
      (node (ref "U2") (pin "7") (pinfunction "A_7") (pintype "passive"))
    )
    (net (code "55") (name "Net-(R21-Pad2)") (class "Default")
      (node (ref "R21") (pin "2") (pinfunction "2_2") (pintype "passive"))
      (node (ref "U3") (pin "1") (pinfunction "A_1") (pintype "passive"))
    )
    (net (code "56") (name "Net-(R23-Pad2)") (class "Default")
      (node (ref "R23") (pin "2") (pinfunction "2_2") (pintype "passive"))
      (node (ref "U3") (pin "3") (pinfunction "A_3") (pintype "passive"))
    )
    (net (code "57") (name "Net-(U4-VCAP)") (class "Default")
      (node (ref "C5") (pin "2") (pinfunction "2_2") (pintype "passive"))
      (node (ref "U4") (pin "7") (pinfunction "VCAP_7") (pintype "power_in"))
    )
    (net (code "58") (name "Net-(U5A-INA+)") (class "Default")
      (node (ref "C9") (pin "2") (pinfunction "2_2") (pintype "passive"))
      (node (ref "R27") (pin "1") (pinfunction "1_1") (pintype "passive"))
      (node (ref "R29") (pin "2") (pinfunction "2_2") (pintype "passive"))
      (node (ref "U5") (pin "3") (pinfunction "INA+_3") (pintype "input"))
    )
    (net (code "59") (name "Net-(U5A-INA-)") (class "Default")
      (node (ref "U5") (pin "1") (pinfunction "OUTA_1") (pintype "output"))
      (node (ref "U5") (pin "2") (pinfunction "INA-_2") (pintype "input"))
      (node (ref "U5") (pin "5") (pinfunction "INB+_5") (pintype "input"))
      (node (ref "VREF1") (pin "1") (pinfunction "1_1") (pintype "passive"))
    )
    (net (code "60") (name "Net-(U5B-INB-)") (class "Default")
      (node (ref "C6") (pin "2") (pinfunction "2_2") (pintype "passive"))
      (node (ref "R26") (pin "1") (pinfunction "1_1") (pintype "passive"))
      (node (ref "R28") (pin "2") (pinfunction "2_2") (pintype "passive"))
      (node (ref "U5") (pin "6") (pinfunction "INB-_6") (pintype "input"))
    )
    (net (code "61") (name "Net-(U5B-OUTB)") (class "Default")
      (node (ref "C6") (pin "1") (pinfunction "1_1") (pintype "passive"))
      (node (ref "C8") (pin "2") (pinfunction "2_2") (pintype "passive"))
      (node (ref "R26") (pin "2") (pinfunction "2_2") (pintype "passive"))
      (node (ref "U5") (pin "7") (pinfunction "OUTB_7") (pintype "output"))
    )
    (net (code "62") (name "Net-(U6-VFB)") (class "Default")
      (node (ref "C7") (pin "2") (pinfunction "2_2") (pintype "passive"))
      (node (ref "R28") (pin "1") (pinfunction "1_1") (pintype "passive"))
      (node (ref "TP12") (pin "1") (pinfunction "1_1") (pintype "passive"))
      (node (ref "U6") (pin "2") (pinfunction "VREFOUT_2") (pintype "passive"))
      (node (ref "U6") (pin "3") (pinfunction "VFB_3") (pintype "passive"))
      (node (ref "U6") (pin "4") (pinfunction "VOUT_4") (pintype "passive"))
    )
    (net (code "63") (name "Net-(U10-BIAS)") (class "Default")
      (node (ref "C13") (pin "2") (pinfunction "2_2") (pintype "passive"))
      (node (ref "U10") (pin "2") (pinfunction "BIAS_2") (pintype "passive"))
    )
    (net (code "64") (name "Net-(U10-INN)") (class "Default")
      (node (ref "C12") (pin "2") (pinfunction "2_2") (pintype "passive"))
      (node (ref "U10") (pin "4") (pinfunction "INN_4") (pintype "passive"))
    )
    (net (code "65") (name "Net-(U10-INP)") (class "Default")
      (node (ref "C7") (pin "1") (pinfunction "1_1") (pintype "passive"))
      (node (ref "U10") (pin "3") (pinfunction "INP_3") (pintype "passive"))
    )
    (net (code "66") (name "Net-(U10-OUTN)") (class "Default")
      (node (ref "LS1") (pin "1") (pinfunction "1_1") (pintype "passive"))
      (node (ref "TP10") (pin "1") (pinfunction "1_1") (pintype "passive"))
      (node (ref "U10") (pin "8") (pinfunction "OUTN_8") (pintype "passive"))
    )
    (net (code "67") (name "Net-(U10-OUTP)") (class "Default")
      (node (ref "LS1") (pin "2") (pinfunction "2_2") (pintype "passive"))
      (node (ref "U10") (pin "5") (pinfunction "OUTP_5") (pintype "passive"))
    )
    (net (code "68") (name "Net-(U10-SDB)") (class "Default")
      (node (ref "P12") (pin "1") (pinfunction "1_1") (pintype "passive"))
      (node (ref "U10") (pin "1") (pinfunction "SDB_1") (pintype "passive"))
    )
    (net (code "69") (name "unconnected-(J1-DAT1-Pad8)") (class "Default")
      (node (ref "J1") (pin "8") (pinfunction "DAT1_8") (pintype "bidirectional+no_connect"))
    )
    (net (code "70") (name "unconnected-(J2-Pad3)") (class "Default")
      (node (ref "J2") (pin "3") (pinfunction "3_3") (pintype "passive"))
    )
    (net (code "71") (name "unconnected-(P9-Pad6)") (class "Default")
      (node (ref "P9") (pin "6") (pinfunction "6_6") (pintype "passive+no_connect"))
    )
    (net (code "72") (name "unconnected-(U3-A-Pad5)") (class "Default")
      (node (ref "U3") (pin "5") (pinfunction "A_5") (pintype "passive+no_connect"))
    )
    (net (code "73") (name "unconnected-(U3-A-Pad7)") (class "Default")
      (node (ref "U3") (pin "7") (pinfunction "A_7") (pintype "passive+no_connect"))
    )
    (net (code "74") (name "unconnected-(U3-C-Pad6)") (class "Default")
      (node (ref "U3") (pin "6") (pinfunction "C_6") (pintype "passive+no_connect"))
    )
    (net (code "75") (name "unconnected-(U3-C-Pad8)") (class "Default")
      (node (ref "U3") (pin "8") (pinfunction "C_8") (pintype "passive+no_connect"))
    )
    (net (code "76") (name "unconnected-(U3-CO-Pad10)") (class "Default")
      (node (ref "U3") (pin "10") (pinfunction "CO_10") (pintype "passive+no_connect"))
    )
    (net (code "77") (name "unconnected-(U3-CO-Pad12)") (class "Default")
      (node (ref "U3") (pin "12") (pinfunction "CO_12") (pintype "passive+no_connect"))
    )
    (net (code "78") (name "unconnected-(U3-E-Pad9)") (class "Default")
      (node (ref "U3") (pin "9") (pinfunction "E_9") (pintype "passive+no_connect"))
    )
    (net (code "79") (name "unconnected-(U3-E-Pad11)") (class "Default")
      (node (ref "U3") (pin "11") (pinfunction "E_11") (pintype "passive+no_connect"))
    )
    (net (code "80") (name "unconnected-(U4-AN4{slash}C1INB{slash}C2IND{slash}RPB2{slash}SDA2{slash}CTED13{slash}PMD2{slash}RB2-Pad23)") (class "Default")
      (node (ref "U4") (pin "23") (pinfunction "AN4/C1INB/C2IND/RPB2/SDA2/CTED13/PMD2/RB2_23") (pintype "input+no_connect"))
    )
    (net (code "81") (name "unconnected-(U4-AN5{slash}C1INA{slash}C2INC{slash}RTCC{slash}RPB3{slash}SCL2{slash}PMWR{slash}RB3-Pad24)") (class "Default")
      (node (ref "U4") (pin "24") (pinfunction "AN5/C1INA/C2INC/RTCC/RPB3/SCL2/PMWR/RB3_24") (pintype "input+no_connect"))
    )
    (net (code "82") (name "unconnected-(U4-PGEC1{slash}AN3{slash}C1INC{slash}C2INA{slash}RPB1{slash}CTED12{slash}PMD1{slash}RB1-Pad22)") (class "Default")
      (node (ref "U4") (pin "22") (pinfunction "PGEC1/AN3/C1INC/C2INA/RPB1/CTED12/PMD1/RB1_22") (pintype "input+no_connect"))
    )
    (net (code "83") (name "unconnected-(U4-PGEC3{slash}VREF-{slash}CVREF-{slash}AN1{slash}RPA1{slash}CTED2{slash}PMD6{slash}RA1-Pad20)") (class "Default")
      (node (ref "U4") (pin "20") (pinfunction "PGEC3/VREF-/CVREF-/AN1/RPA1/CTED2/PMD6/RA1_20") (pintype "power_in+no_connect"))
    )
    (net (code "84") (name "unconnected-(U4-PGED1{slash}AN2{slash}C1IND{slash}C2INB{slash}C3IND{slash}RPB0{slash}PMD0{slash}RB0-Pad21)") (class "Default")
      (node (ref "U4") (pin "21") (pinfunction "PGED1/AN2/C1IND/C2INB/C3IND/RPB0/PMD0/RB0_21") (pintype "input+no_connect"))
    )
    (net (code "85") (name "unconnected-(U4-RPB5{slash}USBID{slash}RB5-Pad41)") (class "Default")
      (node (ref "U4") (pin "41") (pinfunction "RPB5/USBID/RB5_41") (pintype "bidirectional+no_connect"))
    )
    (net (code "86") (name "unconnected-(U4-RPB7{slash}CTED3{slash}PMD5{slash}INT0{slash}RB7-Pad43)") (class "Default")
      (node (ref "U4") (pin "43") (pinfunction "RPB7/CTED3/PMD5/INT0/RB7_43") (pintype "bidirectional"))
    )
    (net (code "87") (name "unconnected-(U4-RPB8{slash}SCL1{slash}CTED10{slash}PMD4{slash}RB8-Pad44)") (class "Default")
      (node (ref "U4") (pin "44") (pinfunction "RPB8/SCL1/CTED10/PMD4/RB8_44") (pintype "bidirectional"))
    )
    (net (code "88") (name "unconnected-(U4-RPC7{slash}PMA0{slash}RC7-Pad3)") (class "Default")
      (node (ref "U4") (pin "3") (pinfunction "RPC7/PMA0/RC7_3") (pintype "bidirectional+no_connect"))
    )
    (net (code "89") (name "unconnected-(U4-SOSCI{slash}RPB4{slash}RB4-Pad33)") (class "Default")
      (node (ref "U4") (pin "33") (pinfunction "SOSCI/RPB4/RB4_33") (pintype "passive+no_connect"))
    )
    (net (code "90") (name "unconnected-(U4-SOSCO{slash}RPA4{slash}T1CK{slash}CTED9{slash}RA4-Pad34)") (class "Default")
      (node (ref "U4") (pin "34") (pinfunction "SOSCO/RPA4/T1CK/CTED9/RA4_34") (pintype "bidirectional+no_connect"))
    )
    (net (code "91") (name "unconnected-(U4-TDI{slash}RPA9{slash}PMA9{slash}RA9-Pad35)") (class "Default")
      (node (ref "U4") (pin "35") (pinfunction "TDI/RPA9/PMA9/RA9_35") (pintype "passive+no_connect"))
    )
    (net (code "92") (name "unconnected-(U4-TDO{slash}RPA8{slash}PMA8{slash}RA8-Pad32)") (class "Default")
      (node (ref "U4") (pin "32") (pinfunction "TDO/RPA8/PMA8/RA8_32") (pintype "passive+no_connect"))
    )
    (net (code "93") (name "unconnected-(U4-VBUS-Pad42)") (class "Default")
      (node (ref "U4") (pin "42") (pinfunction "VBUS_42") (pintype "passive+no_connect"))
    )
  )
)
